# midicontrol.net
KiCad netlist of a schematic drawn in EAGLE
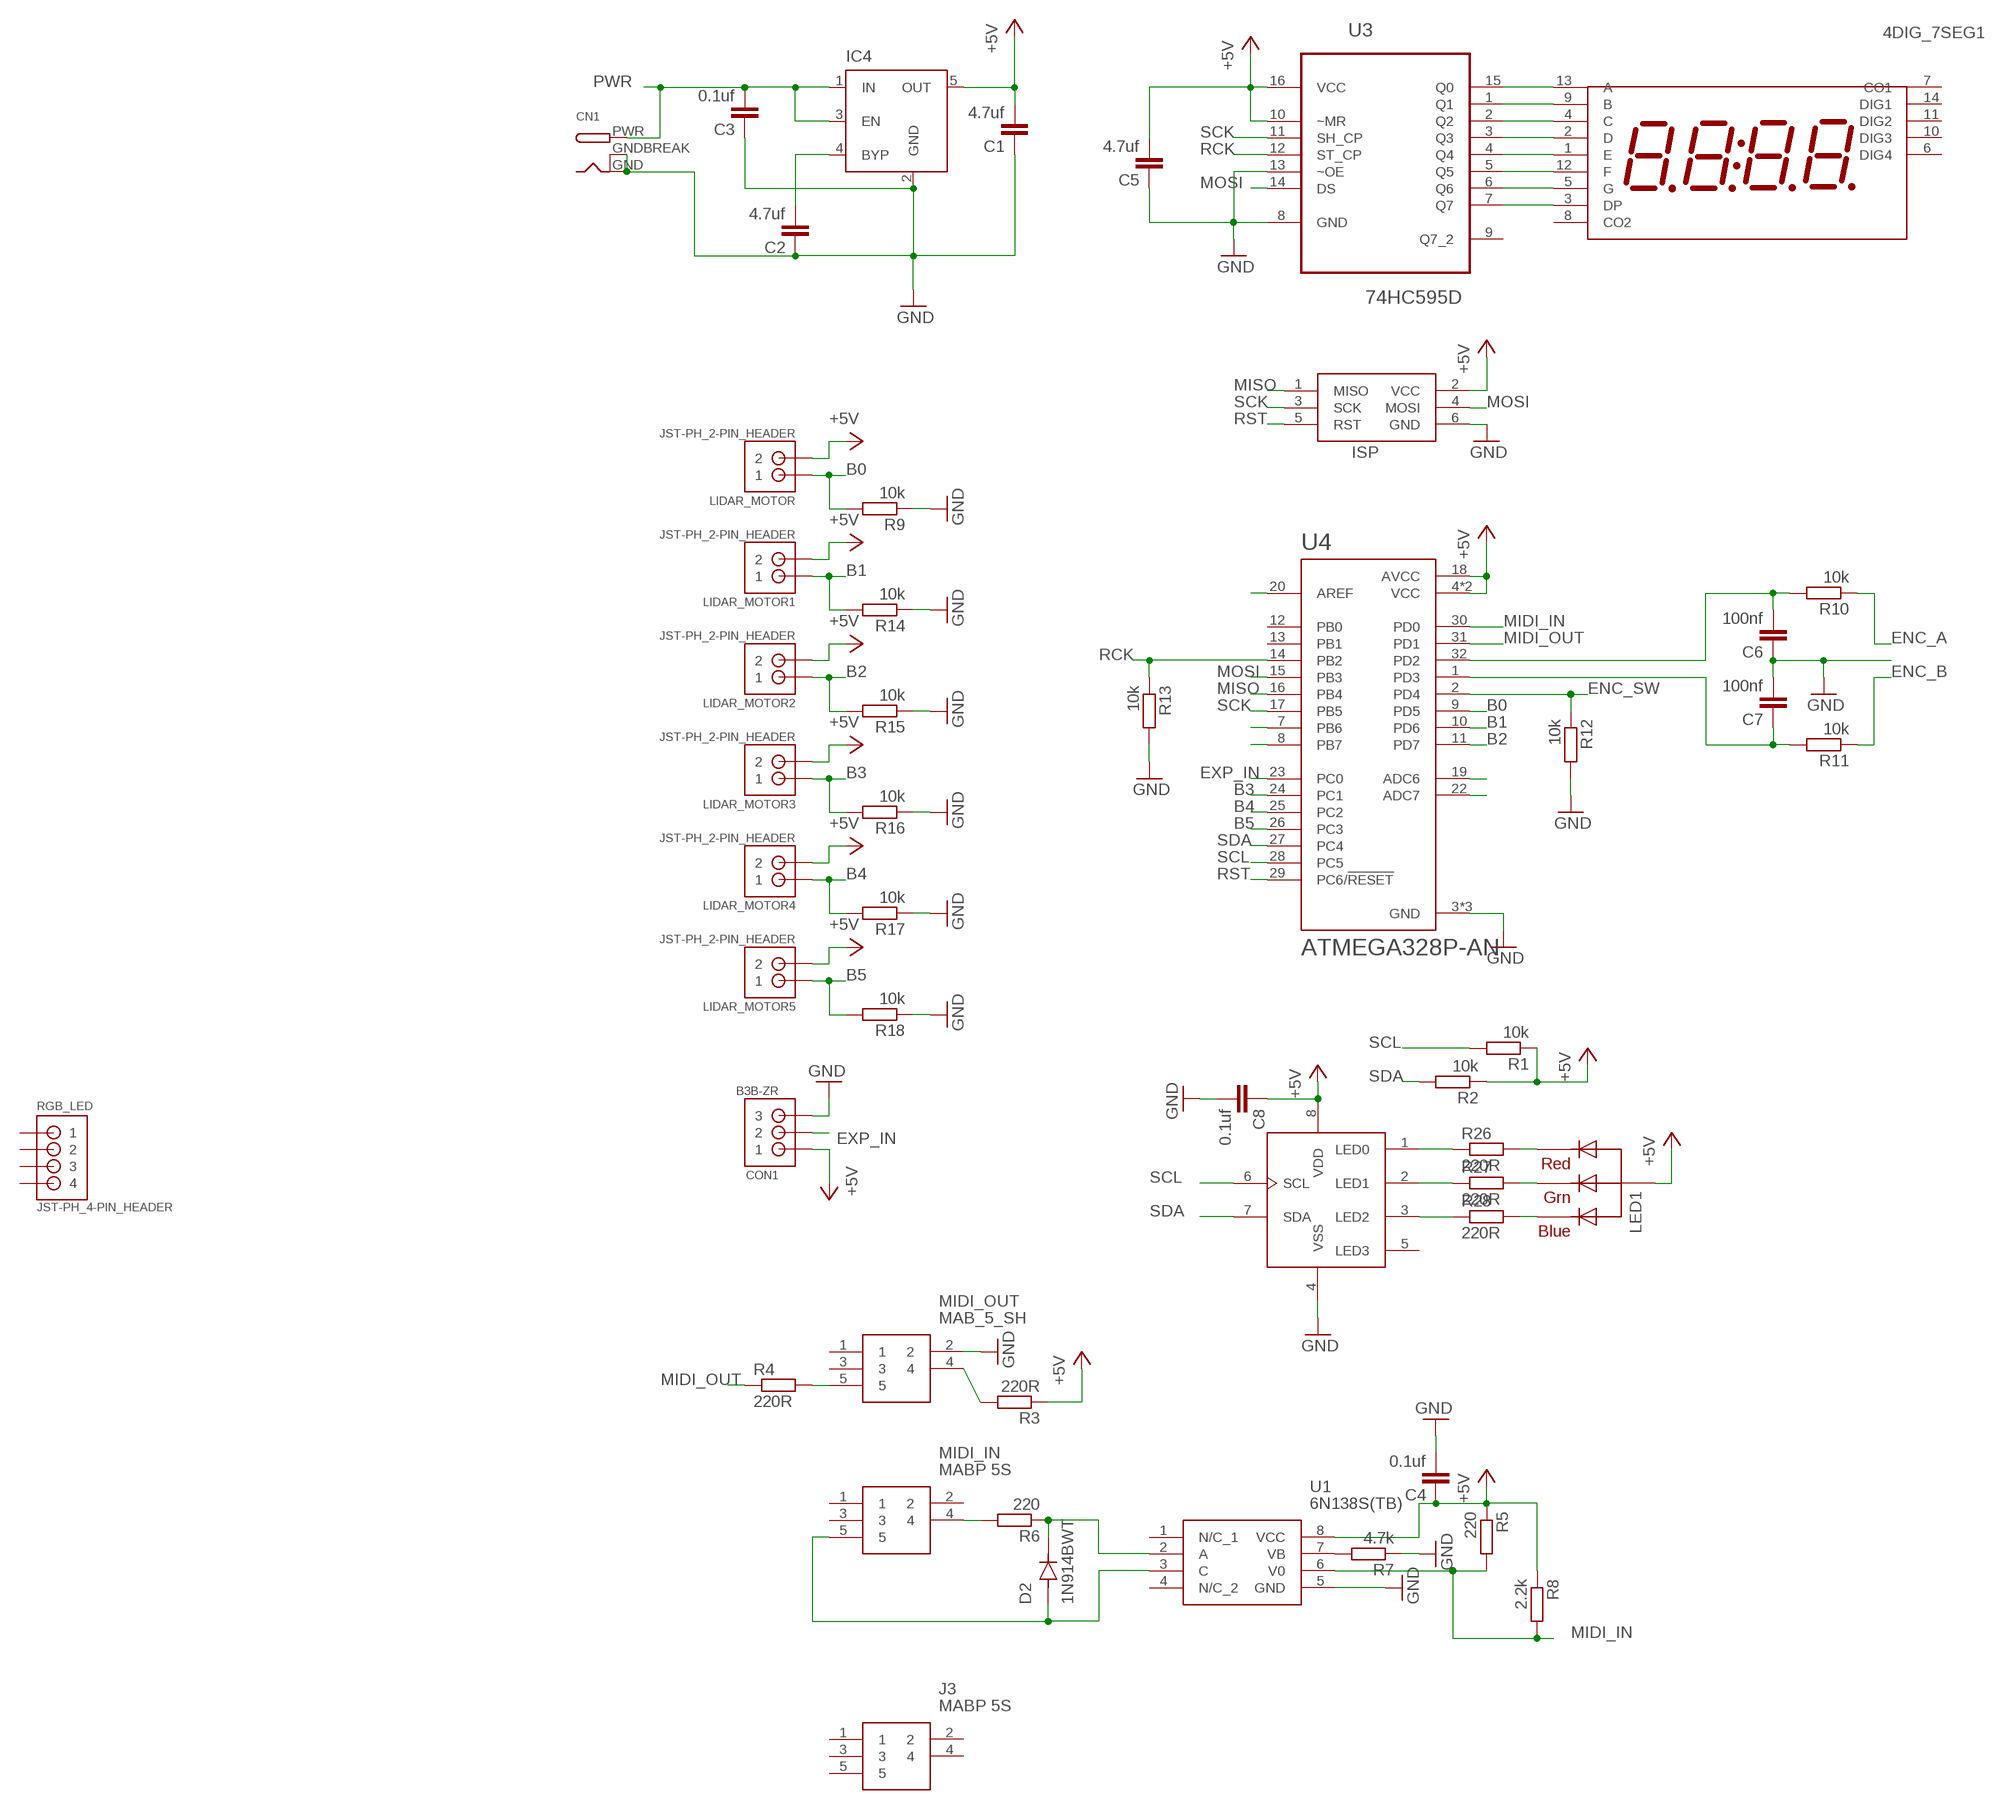
[diagram p0: schematic, sheet 1]

(export (version "E")
  (design (tool "Eeschema 10.0.6"))
  (components
    (comp (ref "4DIG_7SEG1")
      (value "4DIG_7SEG")
      (footprint "eagle-import:4DIG_7SEG")
      (libsource (lib "eagle-import") (part "4DIG_7SEG"))
    )
    (comp (ref "C1")
      (value "4.7uf")
      (footprint "eagle-import:C1206")
      (libsource (lib "eagle-import") (part "C-EUC1206"))
    )
    (comp (ref "C2")
      (value "4.7uf")
      (footprint "eagle-import:C1206")
      (libsource (lib "eagle-import") (part "C-EUC1206"))
    )
    (comp (ref "C3")
      (value "0.1uf")
      (footprint "eagle-import:C1206")
      (libsource (lib "eagle-import") (part "C-EUC1206"))
    )
    (comp (ref "C4")
      (value "0.1uf")
      (footprint "eagle-import:C1206")
      (libsource (lib "eagle-import") (part "C-EUC1206"))
    )
    (comp (ref "C5")
      (value "4.7uf")
      (footprint "eagle-import:C1206")
      (libsource (lib "eagle-import") (part "C-EUC1206"))
    )
    (comp (ref "C6")
      (value "100nf")
      (footprint "eagle-import:C1206")
      (libsource (lib "eagle-import") (part "C-EUC1206"))
    )
    (comp (ref "C7")
      (value "100nf")
      (footprint "eagle-import:C1206")
      (libsource (lib "eagle-import") (part "C-EUC1206"))
    )
    (comp (ref "C8")
      (value "0.1uf")
      (footprint "eagle-import:C1206")
      (libsource (lib "eagle-import") (part "C-EUC1206"))
    )
    (comp (ref "CN1")
      (value "DCBARRELPTH")
      (footprint "eagle-import:DCJACK_2MM_PTH")
      (libsource (lib "eagle-import") (part "DCBARRELPTH"))
    )
    (comp (ref "CON1")
      (value "B3B-ZR")
      (footprint "eagle-import:B3B-ZR")
      (libsource (lib "eagle-import") (part "B3B-ZR"))
    )
    (comp (ref "D2")
      (value "1N914BWT")
      (footprint "eagle-import:SODFL1608X70N")
      (fields (field (name "MF") "ON Semiconductor"))
      (libsource (lib "eagle-import") (part "1N914BWT"))
    )
    (comp (ref "IC4")
      (value "MIC5219XX")
      (footprint "eagle-import:SOT23-5")
      (libsource (lib "eagle-import") (part "MIC5219XX"))
    )
    (comp (ref "ISP")
      (value "AVRISP-6")
      (footprint "eagle-import:AVRISP")
      (libsource (lib "eagle-import") (part "AVRISP-6"))
    )
    (comp (ref "J3")
      (value "MABP 5S")
      (footprint "eagle-import:MAB-5-SH")
      (fields (field (name "MANUFACTURER_PART_NUMBER") "MAB 5 SH"))
      (libsource (lib "eagle-import") (part "MAB_5_SH"))
    )
    (comp (ref "LED1")
      (value "RGBLED_CA-5MM")
      (footprint "eagle-import:LED5MMRGB")
      (libsource (lib "eagle-import") (part "RGBLED_CA-5MM"))
    )
    (comp (ref "LIDAR_MOTOR")
      (value "JST-PH_2-PIN_HEADER")
      (footprint "eagle-import:JST_B2B-PH_HEADER")
      (libsource (lib "eagle-import") (part "JST-PH_2-PIN_HEADER"))
    )
    (comp (ref "LIDAR_MOTOR1")
      (value "JST-PH_2-PIN_HEADER")
      (footprint "eagle-import:JST_B2B-PH_HEADER")
      (libsource (lib "eagle-import") (part "JST-PH_2-PIN_HEADER"))
    )
    (comp (ref "LIDAR_MOTOR2")
      (value "JST-PH_2-PIN_HEADER")
      (footprint "eagle-import:JST_B2B-PH_HEADER")
      (libsource (lib "eagle-import") (part "JST-PH_2-PIN_HEADER"))
    )
    (comp (ref "LIDAR_MOTOR3")
      (value "JST-PH_2-PIN_HEADER")
      (footprint "eagle-import:JST_B2B-PH_HEADER")
      (libsource (lib "eagle-import") (part "JST-PH_2-PIN_HEADER"))
    )
    (comp (ref "LIDAR_MOTOR4")
      (value "JST-PH_2-PIN_HEADER")
      (footprint "eagle-import:JST_B2B-PH_HEADER")
      (libsource (lib "eagle-import") (part "JST-PH_2-PIN_HEADER"))
    )
    (comp (ref "LIDAR_MOTOR5")
      (value "JST-PH_2-PIN_HEADER")
      (footprint "eagle-import:JST_B2B-PH_HEADER")
      (libsource (lib "eagle-import") (part "JST-PH_2-PIN_HEADER"))
    )
    (comp (ref "MIDI_IN")
      (value "MABP 5S")
      (footprint "eagle-import:MAB-5-SH")
      (fields (field (name "MANUFACTURER_PART_NUMBER") "MAB 5 SH"))
      (libsource (lib "eagle-import") (part "MAB_5_SH"))
    )
    (comp (ref "MIDI_OUT")
      (value "MAB_5_SH")
      (footprint "eagle-import:MAB-5-SH")
      (fields (field (name "MANUFACTURER_PART_NUMBER") "MAB 5 SH"))
      (libsource (lib "eagle-import") (part "MAB_5_SH"))
    )
    (comp (ref "PCA9533")
      (value "PCA9533")
      (footprint "eagle-import:SOIC8")
      (libsource (lib "eagle-import") (part "PCA9533"))
    )
    (comp (ref "R1")
      (value "10k")
      (footprint "eagle-import:R0603")
      (libsource (lib "eagle-import") (part "R-EU_R0603"))
    )
    (comp (ref "R2")
      (value "10k")
      (footprint "eagle-import:R0603")
      (libsource (lib "eagle-import") (part "R-EU_R0603"))
    )
    (comp (ref "R3")
      (value "220R")
      (footprint "eagle-import:R0603")
      (libsource (lib "eagle-import") (part "R-EU_R0603"))
    )
    (comp (ref "R4")
      (value "220R")
      (footprint "eagle-import:R0603")
      (libsource (lib "eagle-import") (part "R-EU_R0603"))
    )
    (comp (ref "R5")
      (value "220")
      (footprint "eagle-import:R0603")
      (libsource (lib "eagle-import") (part "R-EU_R0603"))
    )
    (comp (ref "R6")
      (value "220")
      (footprint "eagle-import:R0603")
      (libsource (lib "eagle-import") (part "R-EU_R0603"))
    )
    (comp (ref "R7")
      (value "4.7k")
      (footprint "eagle-import:R0603")
      (libsource (lib "eagle-import") (part "R-EU_R0603"))
    )
    (comp (ref "R8")
      (value "2.2k")
      (footprint "eagle-import:R0603")
      (libsource (lib "eagle-import") (part "R-EU_R0603"))
    )
    (comp (ref "R9")
      (value "10k")
      (footprint "eagle-import:R0603")
      (libsource (lib "eagle-import") (part "R-EU_R0603"))
    )
    (comp (ref "R10")
      (value "10k")
      (footprint "eagle-import:R0603")
      (libsource (lib "eagle-import") (part "R-EU_R0603"))
    )
    (comp (ref "R11")
      (value "10k")
      (footprint "eagle-import:R0603")
      (libsource (lib "eagle-import") (part "R-EU_R0603"))
    )
    (comp (ref "R12")
      (value "10k")
      (footprint "eagle-import:R0603")
      (libsource (lib "eagle-import") (part "R-EU_R0603"))
    )
    (comp (ref "R13")
      (value "10k")
      (footprint "eagle-import:R0603")
      (libsource (lib "eagle-import") (part "R-EU_R0603"))
    )
    (comp (ref "R14")
      (value "10k")
      (footprint "eagle-import:R0603")
      (libsource (lib "eagle-import") (part "R-EU_R0603"))
    )
    (comp (ref "R15")
      (value "10k")
      (footprint "eagle-import:R0603")
      (libsource (lib "eagle-import") (part "R-EU_R0603"))
    )
    (comp (ref "R16")
      (value "10k")
      (footprint "eagle-import:R0603")
      (libsource (lib "eagle-import") (part "R-EU_R0603"))
    )
    (comp (ref "R17")
      (value "10k")
      (footprint "eagle-import:R0603")
      (libsource (lib "eagle-import") (part "R-EU_R0603"))
    )
    (comp (ref "R18")
      (value "10k")
      (footprint "eagle-import:R0603")
      (libsource (lib "eagle-import") (part "R-EU_R0603"))
    )
    (comp (ref "R26")
      (value "220R")
      (footprint "eagle-import:R0603")
      (libsource (lib "eagle-import") (part "R-EU_R0603"))
    )
    (comp (ref "R27")
      (value "220R")
      (footprint "eagle-import:R0603")
      (libsource (lib "eagle-import") (part "R-EU_R0603"))
    )
    (comp (ref "R28")
      (value "220R")
      (footprint "eagle-import:R0603")
      (libsource (lib "eagle-import") (part "R-EU_R0603"))
    )
    (comp (ref "RGB_LED")
      (value "JST-PH_4-PIN_HEADER")
      (footprint "eagle-import:JST_B4B-PH_HEADER")
      (libsource (lib "eagle-import") (part "JST-PH_4-PIN_HEADER"))
    )
    (comp (ref "U1")
      (value "6N138S(TB)")
      (footprint "eagle-import:SOP254P1030X460-8N")
      (fields (field (name "MOUSER_PART_NUMBER") "638-6N138STB"))
      (libsource (lib "eagle-import") (part "6N138S(TB)"))
    )
    (comp (ref "U3")
      (value "74HC595D")
      (footprint "eagle-import:SOIC127P600X175-16N")
      (fields (field (name "MF") "Toshiba Semiconductor"))
      (libsource (lib "eagle-import") (part "74HC595D"))
    )
    (comp (ref "U4")
      (value "ATMEGA328P-AN")
      (footprint "eagle-import:QFP80P900X900X120-32N")
      (fields (field (name "MF") "Microchip"))
      (libsource (lib "eagle-import") (part "ATMEGA328P-AN"))
    )
  )
  (nets
    (net (code "1") (name "+5V") (class "Default")
      (node (ref "C1") (pin "2") (pinfunction "2_2") (pintype "passive"))
      (node (ref "C4") (pin "1") (pinfunction "1_1") (pintype "passive"))
      (node (ref "C5") (pin "2") (pinfunction "2_2") (pintype "passive"))
      (node (ref "C8") (pin "1") (pinfunction "1_1") (pintype "passive"))
      (node (ref "CON1") (pin "1") (pinfunction "1_1") (pintype "bidirectional"))
      (node (ref "IC4") (pin "5") (pinfunction "OUT_5") (pintype "output"))
      (node (ref "ISP") (pin "2") (pinfunction "VCC_2") (pintype "power_in"))
      (node (ref "LED1") (pin "2") (pinfunction "VCC_2") (pintype "bidirectional"))
      (node (ref "LIDAR_MOTOR") (pin "P2") (pinfunction "2_P2") (pintype "bidirectional"))
      (node (ref "LIDAR_MOTOR1") (pin "P2") (pinfunction "2_P2") (pintype "bidirectional"))
      (node (ref "LIDAR_MOTOR2") (pin "P2") (pinfunction "2_P2") (pintype "bidirectional"))
      (node (ref "LIDAR_MOTOR3") (pin "P2") (pinfunction "2_P2") (pintype "bidirectional"))
      (node (ref "LIDAR_MOTOR4") (pin "P2") (pinfunction "2_P2") (pintype "bidirectional"))
      (node (ref "LIDAR_MOTOR5") (pin "P2") (pinfunction "2_P2") (pintype "bidirectional"))
      (node (ref "PCA9533") (pin "8") (pinfunction "VDD_8") (pintype "power_in"))
      (node (ref "R1") (pin "1") (pinfunction "1_1") (pintype "passive"))
      (node (ref "R2") (pin "1") (pinfunction "1_1") (pintype "passive"))
      (node (ref "R3") (pin "1") (pinfunction "1_1") (pintype "passive"))
      (node (ref "R5") (pin "1") (pinfunction "1_1") (pintype "passive"))
      (node (ref "R8") (pin "1") (pinfunction "1_1") (pintype "passive"))
      (node (ref "U1") (pin "8") (pinfunction "VCC_8") (pintype "power_in"))
      (node (ref "U3") (pin "10") (pinfunction "~{MR}_10") (pintype "passive"))
      (node (ref "U3") (pin "16") (pinfunction "VCC_16") (pintype "power_in"))
      (node (ref "U4") (pin "18") (pinfunction "AVCC_18") (pintype "power_in"))
      (node (ref "U4") (pin "4") (pinfunction "VCC_4") (pintype "power_in"))
      (node (ref "U4") (pin "6") (pinfunction "VCC_6") (pintype "power_in"))
    )
    (net (code "2") (name "/B0") (class "Default")
      (node (ref "LIDAR_MOTOR") (pin "P1") (pinfunction "1_P1") (pintype "bidirectional"))
      (node (ref "R9") (pin "2") (pinfunction "2_2") (pintype "passive"))
      (node (ref "U4") (pin "9") (pinfunction "PD5_9") (pintype "bidirectional"))
    )
    (net (code "3") (name "/B1") (class "Default")
      (node (ref "LIDAR_MOTOR1") (pin "P1") (pinfunction "1_P1") (pintype "bidirectional"))
      (node (ref "R14") (pin "2") (pinfunction "2_2") (pintype "passive"))
      (node (ref "U4") (pin "10") (pinfunction "PD6_10") (pintype "bidirectional"))
    )
    (net (code "4") (name "/B2") (class "Default")
      (node (ref "LIDAR_MOTOR2") (pin "P1") (pinfunction "1_P1") (pintype "bidirectional"))
      (node (ref "R15") (pin "2") (pinfunction "2_2") (pintype "passive"))
      (node (ref "U4") (pin "11") (pinfunction "PD7_11") (pintype "bidirectional"))
    )
    (net (code "5") (name "/B3") (class "Default")
      (node (ref "LIDAR_MOTOR3") (pin "P1") (pinfunction "1_P1") (pintype "bidirectional"))
      (node (ref "R16") (pin "2") (pinfunction "2_2") (pintype "passive"))
      (node (ref "U4") (pin "24") (pinfunction "PC1_24") (pintype "bidirectional"))
    )
    (net (code "6") (name "/B4") (class "Default")
      (node (ref "LIDAR_MOTOR4") (pin "P1") (pinfunction "1_P1") (pintype "bidirectional"))
      (node (ref "R17") (pin "2") (pinfunction "2_2") (pintype "passive"))
      (node (ref "U4") (pin "25") (pinfunction "PC2_25") (pintype "bidirectional"))
    )
    (net (code "7") (name "/B5") (class "Default")
      (node (ref "LIDAR_MOTOR5") (pin "P1") (pinfunction "1_P1") (pintype "bidirectional"))
      (node (ref "R18") (pin "2") (pinfunction "2_2") (pintype "passive"))
      (node (ref "U4") (pin "26") (pinfunction "PC3_26") (pintype "bidirectional"))
    )
    (net (code "8") (name "/ENC_A") (class "Default")
      (node (ref "C7") (pin "1") (pinfunction "1_1") (pintype "passive"))
      (node (ref "R10") (pin "1") (pinfunction "1_1") (pintype "passive"))
      (node (ref "R11") (pin "2") (pinfunction "2_2") (pintype "passive"))
      (node (ref "U4") (pin "1") (pinfunction "PD3_1") (pintype "bidirectional"))
    )
    (net (code "9") (name "/ENC_B") (class "Default")
      (node (ref "C6") (pin "2") (pinfunction "2_2") (pintype "passive"))
      (node (ref "R10") (pin "2") (pinfunction "2_2") (pintype "passive"))
      (node (ref "R11") (pin "1") (pinfunction "1_1") (pintype "passive"))
      (node (ref "U4") (pin "32") (pinfunction "PD2_32") (pintype "bidirectional"))
    )
    (net (code "10") (name "/ENC_SW") (class "Default")
      (node (ref "R12") (pin "1") (pinfunction "1_1") (pintype "passive"))
      (node (ref "U4") (pin "2") (pinfunction "PD4_2") (pintype "bidirectional"))
    )
    (net (code "11") (name "/EXP_IN") (class "Default")
      (node (ref "CON1") (pin "2") (pinfunction "2_2") (pintype "bidirectional"))
      (node (ref "U4") (pin "23") (pinfunction "PC0_23") (pintype "bidirectional"))
    )
    (net (code "12") (name "/MIDI_IN") (class "Default")
      (node (ref "R5") (pin "2") (pinfunction "2_2") (pintype "passive"))
      (node (ref "R8") (pin "2") (pinfunction "2_2") (pintype "passive"))
      (node (ref "U1") (pin "6") (pinfunction "V0_6") (pintype "bidirectional"))
      (node (ref "U4") (pin "30") (pinfunction "PD0_30") (pintype "bidirectional"))
    )
    (net (code "13") (name "/MIDI_OUT") (class "Default")
      (node (ref "R4") (pin "1") (pinfunction "1_1") (pintype "passive"))
      (node (ref "U4") (pin "31") (pinfunction "PD1_31") (pintype "bidirectional"))
    )
    (net (code "14") (name "/MISO") (class "Default")
      (node (ref "ISP") (pin "1") (pinfunction "MISO_1") (pintype "input"))
      (node (ref "U4") (pin "16") (pinfunction "PB4_16") (pintype "bidirectional"))
    )
    (net (code "15") (name "/MOSI") (class "Default")
      (node (ref "ISP") (pin "4") (pinfunction "MOSI_4") (pintype "output"))
      (node (ref "U3") (pin "14") (pinfunction "DS_14") (pintype "input"))
      (node (ref "U4") (pin "15") (pinfunction "PB3_15") (pintype "bidirectional"))
    )
    (net (code "16") (name "/PWR") (class "Default")
      (node (ref "C3") (pin "2") (pinfunction "2_2") (pintype "passive"))
      (node (ref "CN1") (pin "PWR") (pinfunction "PWR_PWR") (pintype "power_in"))
      (node (ref "IC4") (pin "1") (pinfunction "IN_1") (pintype "input"))
      (node (ref "IC4") (pin "3") (pinfunction "EN_3") (pintype "input"))
    )
    (net (code "17") (name "/RCK") (class "Default")
      (node (ref "R13") (pin "1") (pinfunction "1_1") (pintype "passive"))
      (node (ref "U3") (pin "12") (pinfunction "ST_CP_12") (pintype "passive"))
      (node (ref "U4") (pin "14") (pinfunction "PB2_14") (pintype "bidirectional"))
    )
    (net (code "18") (name "/RST") (class "Default")
      (node (ref "ISP") (pin "5") (pinfunction "RST_5") (pintype "output"))
      (node (ref "U4") (pin "29") (pinfunction "PC6/~{RESET}_29") (pintype "bidirectional"))
    )
    (net (code "19") (name "/SCK") (class "Default")
      (node (ref "ISP") (pin "3") (pinfunction "SCK_3") (pintype "output"))
      (node (ref "U3") (pin "11") (pinfunction "SH_CP_11") (pintype "passive"))
      (node (ref "U4") (pin "17") (pinfunction "PB5_17") (pintype "bidirectional"))
    )
    (net (code "20") (name "/SCL") (class "Default")
      (node (ref "PCA9533") (pin "6") (pinfunction "SCL_6") (pintype "input"))
      (node (ref "R1") (pin "2") (pinfunction "2_2") (pintype "passive"))
      (node (ref "U4") (pin "28") (pinfunction "PC5_28") (pintype "bidirectional"))
    )
    (net (code "21") (name "/SDA") (class "Default")
      (node (ref "PCA9533") (pin "7") (pinfunction "SDA_7") (pintype "bidirectional"))
      (node (ref "R2") (pin "2") (pinfunction "2_2") (pintype "passive"))
      (node (ref "U4") (pin "27") (pinfunction "PC4_27") (pintype "bidirectional"))
    )
    (net (code "22") (name "GND") (class "Default")
      (node (ref "C1") (pin "1") (pinfunction "1_1") (pintype "passive"))
      (node (ref "C2") (pin "1") (pinfunction "1_1") (pintype "passive"))
      (node (ref "C3") (pin "1") (pinfunction "1_1") (pintype "passive"))
      (node (ref "C4") (pin "2") (pinfunction "2_2") (pintype "passive"))
      (node (ref "C5") (pin "1") (pinfunction "1_1") (pintype "passive"))
      (node (ref "C6") (pin "1") (pinfunction "1_1") (pintype "passive"))
      (node (ref "C7") (pin "2") (pinfunction "2_2") (pintype "passive"))
      (node (ref "C8") (pin "2") (pinfunction "2_2") (pintype "passive"))
      (node (ref "CN1") (pin "GND") (pinfunction "GND_GND") (pintype "power_in"))
      (node (ref "CN1") (pin "GNDBREAK") (pinfunction "GNDBREAK_GNDBREAK") (pintype "power_in"))
      (node (ref "CON1") (pin "3") (pinfunction "3_3") (pintype "bidirectional"))
      (node (ref "IC4") (pin "2") (pinfunction "GND_2") (pintype "power_in"))
      (node (ref "ISP") (pin "6") (pinfunction "GND_6") (pintype "power_in"))
      (node (ref "MIDI_OUT") (pin "2") (pinfunction "2_2") (pintype "bidirectional"))
      (node (ref "PCA9533") (pin "4") (pinfunction "VSS_4") (pintype "power_in"))
      (node (ref "R12") (pin "2") (pinfunction "2_2") (pintype "passive"))
      (node (ref "R13") (pin "2") (pinfunction "2_2") (pintype "passive"))
      (node (ref "R14") (pin "1") (pinfunction "1_1") (pintype "passive"))
      (node (ref "R15") (pin "1") (pinfunction "1_1") (pintype "passive"))
      (node (ref "R16") (pin "1") (pinfunction "1_1") (pintype "passive"))
      (node (ref "R17") (pin "1") (pinfunction "1_1") (pintype "passive"))
      (node (ref "R18") (pin "1") (pinfunction "1_1") (pintype "passive"))
      (node (ref "R7") (pin "1") (pinfunction "1_1") (pintype "passive"))
      (node (ref "R9") (pin "1") (pinfunction "1_1") (pintype "passive"))
      (node (ref "U1") (pin "5") (pinfunction "GND_5") (pintype "power_in"))
      (node (ref "U3") (pin "13") (pinfunction "~{OE}_13") (pintype "input"))
      (node (ref "U3") (pin "8") (pinfunction "GND_8") (pintype "passive"))
      (node (ref "U4") (pin "21") (pinfunction "GND_21") (pintype "power_in"))
      (node (ref "U4") (pin "3") (pinfunction "GND_3") (pintype "power_in"))
      (node (ref "U4") (pin "5") (pinfunction "GND_5") (pintype "power_in"))
    )
    (net (code "23") (name "Net-(4DIG_7SEG1-A)") (class "Default")
      (node (ref "4DIG_7SEG1") (pin "13") (pinfunction "A_13") (pintype "bidirectional"))
      (node (ref "U3") (pin "15") (pinfunction "Q0_15") (pintype "output"))
    )
    (net (code "24") (name "Net-(4DIG_7SEG1-B)") (class "Default")
      (node (ref "4DIG_7SEG1") (pin "9") (pinfunction "B_9") (pintype "bidirectional"))
      (node (ref "U3") (pin "1") (pinfunction "Q1_1") (pintype "output"))
    )
    (net (code "25") (name "Net-(4DIG_7SEG1-C)") (class "Default")
      (node (ref "4DIG_7SEG1") (pin "4") (pinfunction "C_4") (pintype "bidirectional"))
      (node (ref "U3") (pin "2") (pinfunction "Q2_2") (pintype "output"))
    )
    (net (code "26") (name "Net-(4DIG_7SEG1-D)") (class "Default")
      (node (ref "4DIG_7SEG1") (pin "2") (pinfunction "D_2") (pintype "bidirectional"))
      (node (ref "U3") (pin "3") (pinfunction "Q3_3") (pintype "output"))
    )
    (net (code "27") (name "Net-(4DIG_7SEG1-DP)") (class "Default")
      (node (ref "4DIG_7SEG1") (pin "3") (pinfunction "DP_3") (pintype "bidirectional"))
      (node (ref "U3") (pin "7") (pinfunction "Q7_7") (pintype "output"))
    )
    (net (code "28") (name "Net-(4DIG_7SEG1-E)") (class "Default")
      (node (ref "4DIG_7SEG1") (pin "1") (pinfunction "E_1") (pintype "bidirectional"))
      (node (ref "U3") (pin "4") (pinfunction "Q4_4") (pintype "output"))
    )
    (net (code "29") (name "Net-(4DIG_7SEG1-F)") (class "Default")
      (node (ref "4DIG_7SEG1") (pin "12") (pinfunction "F_12") (pintype "bidirectional"))
      (node (ref "U3") (pin "5") (pinfunction "Q5_5") (pintype "output"))
    )
    (net (code "30") (name "Net-(4DIG_7SEG1-G)") (class "Default")
      (node (ref "4DIG_7SEG1") (pin "5") (pinfunction "G_5") (pintype "bidirectional"))
      (node (ref "U3") (pin "6") (pinfunction "Q6_6") (pintype "output"))
    )
    (net (code "31") (name "Net-(D2-K)") (class "Default")
      (node (ref "D2") (pin "C") (pinfunction "K_C") (pintype "passive"))
      (node (ref "R6") (pin "1") (pinfunction "1_1") (pintype "passive"))
      (node (ref "U1") (pin "2") (pinfunction "A_2") (pintype "bidirectional"))
    )
    (net (code "32") (name "Net-(IC4-BYP)") (class "Default")
      (node (ref "C2") (pin "2") (pinfunction "2_2") (pintype "passive"))
      (node (ref "IC4") (pin "4") (pinfunction "BYP_4") (pintype "passive"))
    )
    (net (code "33") (name "Net-(LED1-BLUE)") (class "Default")
      (node (ref "LED1") (pin "4") (pinfunction "BLUE_4") (pintype "bidirectional"))
      (node (ref "R28") (pin "2") (pinfunction "2_2") (pintype "passive"))
    )
    (net (code "34") (name "Net-(LED1-GREEN)") (class "Default")
      (node (ref "LED1") (pin "3") (pinfunction "GREEN_3") (pintype "bidirectional"))
      (node (ref "R27") (pin "2") (pinfunction "2_2") (pintype "passive"))
    )
    (net (code "35") (name "Net-(LED1-RED)") (class "Default")
      (node (ref "LED1") (pin "1") (pinfunction "RED_1") (pintype "bidirectional"))
      (node (ref "R26") (pin "2") (pinfunction "2_2") (pintype "passive"))
    )
    (net (code "36") (name "Net-(MIDI_IN-Pad4)") (class "Default")
      (node (ref "MIDI_IN") (pin "4") (pinfunction "4_4") (pintype "bidirectional"))
      (node (ref "R6") (pin "2") (pinfunction "2_2") (pintype "passive"))
    )
    (net (code "37") (name "Net-(MIDI_OUT-Pad4)") (class "Default")
      (node (ref "MIDI_OUT") (pin "4") (pinfunction "4_4") (pintype "bidirectional"))
      (node (ref "R3") (pin "2") (pinfunction "2_2") (pintype "passive"))
    )
    (net (code "38") (name "Net-(MIDI_OUT-Pad5)") (class "Default")
      (node (ref "MIDI_OUT") (pin "5") (pinfunction "5_5") (pintype "bidirectional"))
      (node (ref "R4") (pin "2") (pinfunction "2_2") (pintype "passive"))
    )
    (net (code "39") (name "Net-(PCA9533-LED0)") (class "Default")
      (node (ref "PCA9533") (pin "1") (pinfunction "LED0_1") (pintype "bidirectional"))
      (node (ref "R26") (pin "1") (pinfunction "1_1") (pintype "passive"))
    )
    (net (code "40") (name "Net-(PCA9533-LED1)") (class "Default")
      (node (ref "PCA9533") (pin "2") (pinfunction "LED1_2") (pintype "bidirectional"))
      (node (ref "R27") (pin "1") (pinfunction "1_1") (pintype "passive"))
    )
    (net (code "41") (name "Net-(PCA9533-LED2)") (class "Default")
      (node (ref "PCA9533") (pin "3") (pinfunction "LED2_3") (pintype "bidirectional"))
      (node (ref "R28") (pin "1") (pinfunction "1_1") (pintype "passive"))
    )
    (net (code "42") (name "Net-(U1-C)") (class "Default")
      (node (ref "D2") (pin "A") (pinfunction "A_A") (pintype "passive"))
      (node (ref "MIDI_IN") (pin "5") (pinfunction "5_5") (pintype "bidirectional"))
      (node (ref "U1") (pin "3") (pinfunction "C_3") (pintype "bidirectional"))
    )
    (net (code "43") (name "Net-(U1-VB)") (class "Default")
      (node (ref "R7") (pin "2") (pinfunction "2_2") (pintype "passive"))
      (node (ref "U1") (pin "7") (pinfunction "VB_7") (pintype "bidirectional"))
    )
    (net (code "44") (name "unconnected-(4DIG_7SEG1-CO1-Pad7)") (class "Default")
      (node (ref "4DIG_7SEG1") (pin "7") (pinfunction "CO1_7") (pintype "bidirectional"))
    )
    (net (code "45") (name "unconnected-(4DIG_7SEG1-CO2-Pad8)") (class "Default")
      (node (ref "4DIG_7SEG1") (pin "8") (pinfunction "CO2_8") (pintype "bidirectional"))
    )
    (net (code "46") (name "unconnected-(4DIG_7SEG1-DIG1-Pad14)") (class "Default")
      (node (ref "4DIG_7SEG1") (pin "14") (pinfunction "DIG1_14") (pintype "bidirectional"))
    )
    (net (code "47") (name "unconnected-(4DIG_7SEG1-DIG2-Pad11)") (class "Default")
      (node (ref "4DIG_7SEG1") (pin "11") (pinfunction "DIG2_11") (pintype "bidirectional"))
    )
    (net (code "48") (name "unconnected-(4DIG_7SEG1-DIG3-Pad10)") (class "Default")
      (node (ref "4DIG_7SEG1") (pin "10") (pinfunction "DIG3_10") (pintype "bidirectional"))
    )
    (net (code "49") (name "unconnected-(4DIG_7SEG1-DIG4-Pad6)") (class "Default")
      (node (ref "4DIG_7SEG1") (pin "6") (pinfunction "DIG4_6") (pintype "bidirectional"))
    )
    (net (code "50") (name "unconnected-(J3-Pad1)") (class "Default")
      (node (ref "J3") (pin "1") (pinfunction "1_1") (pintype "bidirectional"))
    )
    (net (code "51") (name "unconnected-(J3-Pad2)") (class "Default")
      (node (ref "J3") (pin "2") (pinfunction "2_2") (pintype "bidirectional"))
    )
    (net (code "52") (name "unconnected-(J3-Pad3)") (class "Default")
      (node (ref "J3") (pin "3") (pinfunction "3_3") (pintype "bidirectional"))
    )
    (net (code "53") (name "unconnected-(J3-Pad4)") (class "Default")
      (node (ref "J3") (pin "4") (pinfunction "4_4") (pintype "bidirectional"))
    )
    (net (code "54") (name "unconnected-(J3-Pad5)") (class "Default")
      (node (ref "J3") (pin "5") (pinfunction "5_5") (pintype "bidirectional"))
    )
    (net (code "55") (name "unconnected-(MIDI_IN-Pad1)") (class "Default")
      (node (ref "MIDI_IN") (pin "1") (pinfunction "1_1") (pintype "bidirectional"))
    )
    (net (code "56") (name "unconnected-(MIDI_IN-Pad2)") (class "Default")
      (node (ref "MIDI_IN") (pin "2") (pinfunction "2_2") (pintype "bidirectional"))
    )
    (net (code "57") (name "unconnected-(MIDI_IN-Pad3)") (class "Default")
      (node (ref "MIDI_IN") (pin "3") (pinfunction "3_3") (pintype "bidirectional"))
    )
    (net (code "58") (name "unconnected-(MIDI_OUT-Pad1)") (class "Default")
      (node (ref "MIDI_OUT") (pin "1") (pinfunction "1_1") (pintype "bidirectional"))
    )
    (net (code "59") (name "unconnected-(MIDI_OUT-Pad3)") (class "Default")
      (node (ref "MIDI_OUT") (pin "3") (pinfunction "3_3") (pintype "bidirectional"))
    )
    (net (code "60") (name "unconnected-(PCA9533-LED3-Pad5)") (class "Default")
      (node (ref "PCA9533") (pin "5") (pinfunction "LED3_5") (pintype "bidirectional"))
    )
    (net (code "61") (name "unconnected-(RGB_LED-1-PadP1)") (class "Default")
      (node (ref "RGB_LED") (pin "P1") (pinfunction "1_P1") (pintype "bidirectional"))
    )
    (net (code "62") (name "unconnected-(RGB_LED-2-PadP2)") (class "Default")
      (node (ref "RGB_LED") (pin "P2") (pinfunction "2_P2") (pintype "bidirectional"))
    )
    (net (code "63") (name "unconnected-(RGB_LED-3-PadP3)") (class "Default")
      (node (ref "RGB_LED") (pin "P3") (pinfunction "3_P3") (pintype "bidirectional"))
    )
    (net (code "64") (name "unconnected-(RGB_LED-4-PadP4)") (class "Default")
      (node (ref "RGB_LED") (pin "P4") (pinfunction "4_P4") (pintype "bidirectional"))
    )
    (net (code "65") (name "unconnected-(U1-N{slash}C_1-Pad1)") (class "Default")
      (node (ref "U1") (pin "1") (pinfunction "N/C_1_1") (pintype "bidirectional"))
    )
    (net (code "66") (name "unconnected-(U1-N{slash}C_2-Pad4)") (class "Default")
      (node (ref "U1") (pin "4") (pinfunction "N/C_2_4") (pintype "bidirectional"))
    )
    (net (code "67") (name "unconnected-(U3-Q7_2-Pad9)") (class "Default")
      (node (ref "U3") (pin "9") (pinfunction "Q7_2_9") (pintype "output"))
    )
    (net (code "68") (name "unconnected-(U4-ADC6-Pad19)") (class "Default")
      (node (ref "U4") (pin "19") (pinfunction "ADC6_19") (pintype "bidirectional"))
    )
    (net (code "69") (name "unconnected-(U4-ADC7-Pad22)") (class "Default")
      (node (ref "U4") (pin "22") (pinfunction "ADC7_22") (pintype "bidirectional"))
    )
    (net (code "70") (name "unconnected-(U4-AREF-Pad20)") (class "Default")
      (node (ref "U4") (pin "20") (pinfunction "AREF_20") (pintype "input"))
    )
    (net (code "71") (name "unconnected-(U4-PB0-Pad12)") (class "Default")
      (node (ref "U4") (pin "12") (pinfunction "PB0_12") (pintype "bidirectional"))
    )
    (net (code "72") (name "unconnected-(U4-PB1-Pad13)") (class "Default")
      (node (ref "U4") (pin "13") (pinfunction "PB1_13") (pintype "bidirectional"))
    )
    (net (code "73") (name "unconnected-(U4-PB6-Pad7)") (class "Default")
      (node (ref "U4") (pin "7") (pinfunction "PB6_7") (pintype "bidirectional"))
    )
    (net (code "74") (name "unconnected-(U4-PB7-Pad8)") (class "Default")
      (node (ref "U4") (pin "8") (pinfunction "PB7_8") (pintype "bidirectional"))
    )
  )
)
